# occupancy-sensor.net
KiCad netlist of a schematic drawn in EAGLE
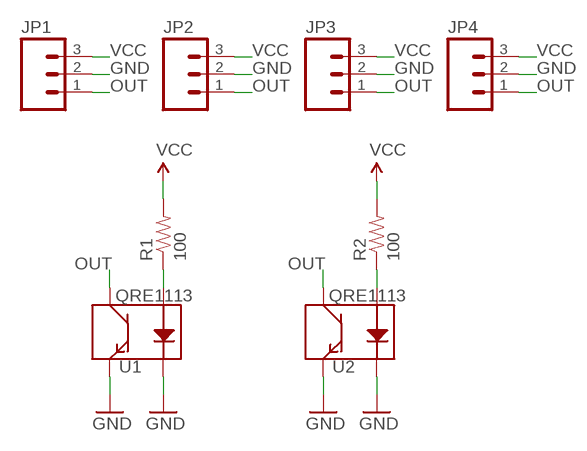
[diagram p0: schematic, sheet 1]

(export (version "E")
  (design (tool "Eeschema 10.0.6"))
  (components
    (comp (ref "JP1")
      (value "M031X03_NO_SILK")
      (footprint "eagle-import:1X03_NO_SILK")
      (libsource (lib "eagle-import") (part "M031X03_NO_SILK"))
    )
    (comp (ref "JP2")
      (value "M031X03_NO_SILK")
      (footprint "eagle-import:1X03_NO_SILK")
      (libsource (lib "eagle-import") (part "M031X03_NO_SILK"))
    )
    (comp (ref "JP3")
      (value "M031X03_NO_SILK")
      (footprint "eagle-import:1X03_NO_SILK")
      (libsource (lib "eagle-import") (part "M031X03_NO_SILK"))
    )
    (comp (ref "JP4")
      (value "M031X03_NO_SILK")
      (footprint "eagle-import:1X03_NO_SILK")
      (libsource (lib "eagle-import") (part "M031X03_NO_SILK"))
    )
    (comp (ref "R1")
      (value "100")
      (footprint "eagle-import:0603-RES")
      (libsource (lib "eagle-import") (part "RESISTOR0603-RES"))
    )
    (comp (ref "R2")
      (value "100")
      (footprint "eagle-import:0603-RES")
      (libsource (lib "eagle-import") (part "RESISTOR0603-RES"))
    )
    (comp (ref "U1")
      (value "QRE1113")
      (footprint "eagle-import:QRE1113-W")
      (libsource (lib "eagle-import") (part "QRE1113SMD-W"))
    )
    (comp (ref "U2")
      (value "QRE1113")
      (footprint "eagle-import:QRE1113-W")
      (libsource (lib "eagle-import") (part "QRE1113SMD-W"))
    )
  )
  (nets
    (net (code "1") (name "/OUT") (class "Default")
      (node (ref "JP1") (pin "1") (pinfunction "1_1") (pintype "passive"))
      (node (ref "JP2") (pin "1") (pinfunction "1_1") (pintype "passive"))
      (node (ref "JP3") (pin "1") (pinfunction "1_1") (pintype "passive"))
      (node (ref "JP4") (pin "1") (pinfunction "1_1") (pintype "passive"))
      (node (ref "U1") (pin "3") (pinfunction "C_3") (pintype "bidirectional"))
      (node (ref "U2") (pin "3") (pinfunction "C_3") (pintype "bidirectional"))
    )
    (net (code "2") (name "GND") (class "Default")
      (node (ref "JP1") (pin "2") (pinfunction "2_2") (pintype "passive"))
      (node (ref "JP2") (pin "2") (pinfunction "2_2") (pintype "passive"))
      (node (ref "JP3") (pin "2") (pinfunction "2_2") (pintype "passive"))
      (node (ref "JP4") (pin "2") (pinfunction "2_2") (pintype "passive"))
      (node (ref "U1") (pin "2") (pinfunction "K_2") (pintype "bidirectional"))
      (node (ref "U1") (pin "4") (pinfunction "E_4") (pintype "bidirectional"))
      (node (ref "U2") (pin "2") (pinfunction "K_2") (pintype "bidirectional"))
      (node (ref "U2") (pin "4") (pinfunction "E_4") (pintype "bidirectional"))
    )
    (net (code "3") (name "Net-(U1-A)") (class "Default")
      (node (ref "R1") (pin "1") (pinfunction "1_1") (pintype "passive"))
      (node (ref "U1") (pin "1") (pinfunction "A_1") (pintype "bidirectional"))
    )
    (net (code "4") (name "Net-(U2-A)") (class "Default")
      (node (ref "R2") (pin "1") (pinfunction "1_1") (pintype "passive"))
      (node (ref "U2") (pin "1") (pinfunction "A_1") (pintype "bidirectional"))
    )
    (net (code "5") (name "VCC") (class "Default")
      (node (ref "JP1") (pin "3") (pinfunction "3_3") (pintype "passive"))
      (node (ref "JP2") (pin "3") (pinfunction "3_3") (pintype "passive"))
      (node (ref "JP3") (pin "3") (pinfunction "3_3") (pintype "passive"))
      (node (ref "JP4") (pin "3") (pinfunction "3_3") (pintype "passive"))
      (node (ref "R1") (pin "2") (pinfunction "2_2") (pintype "passive"))
      (node (ref "R2") (pin "2") (pinfunction "2_2") (pintype "passive"))
    )
  )
)
